# power_converter.net
KiCad netlist of a schematic drawn in EAGLE
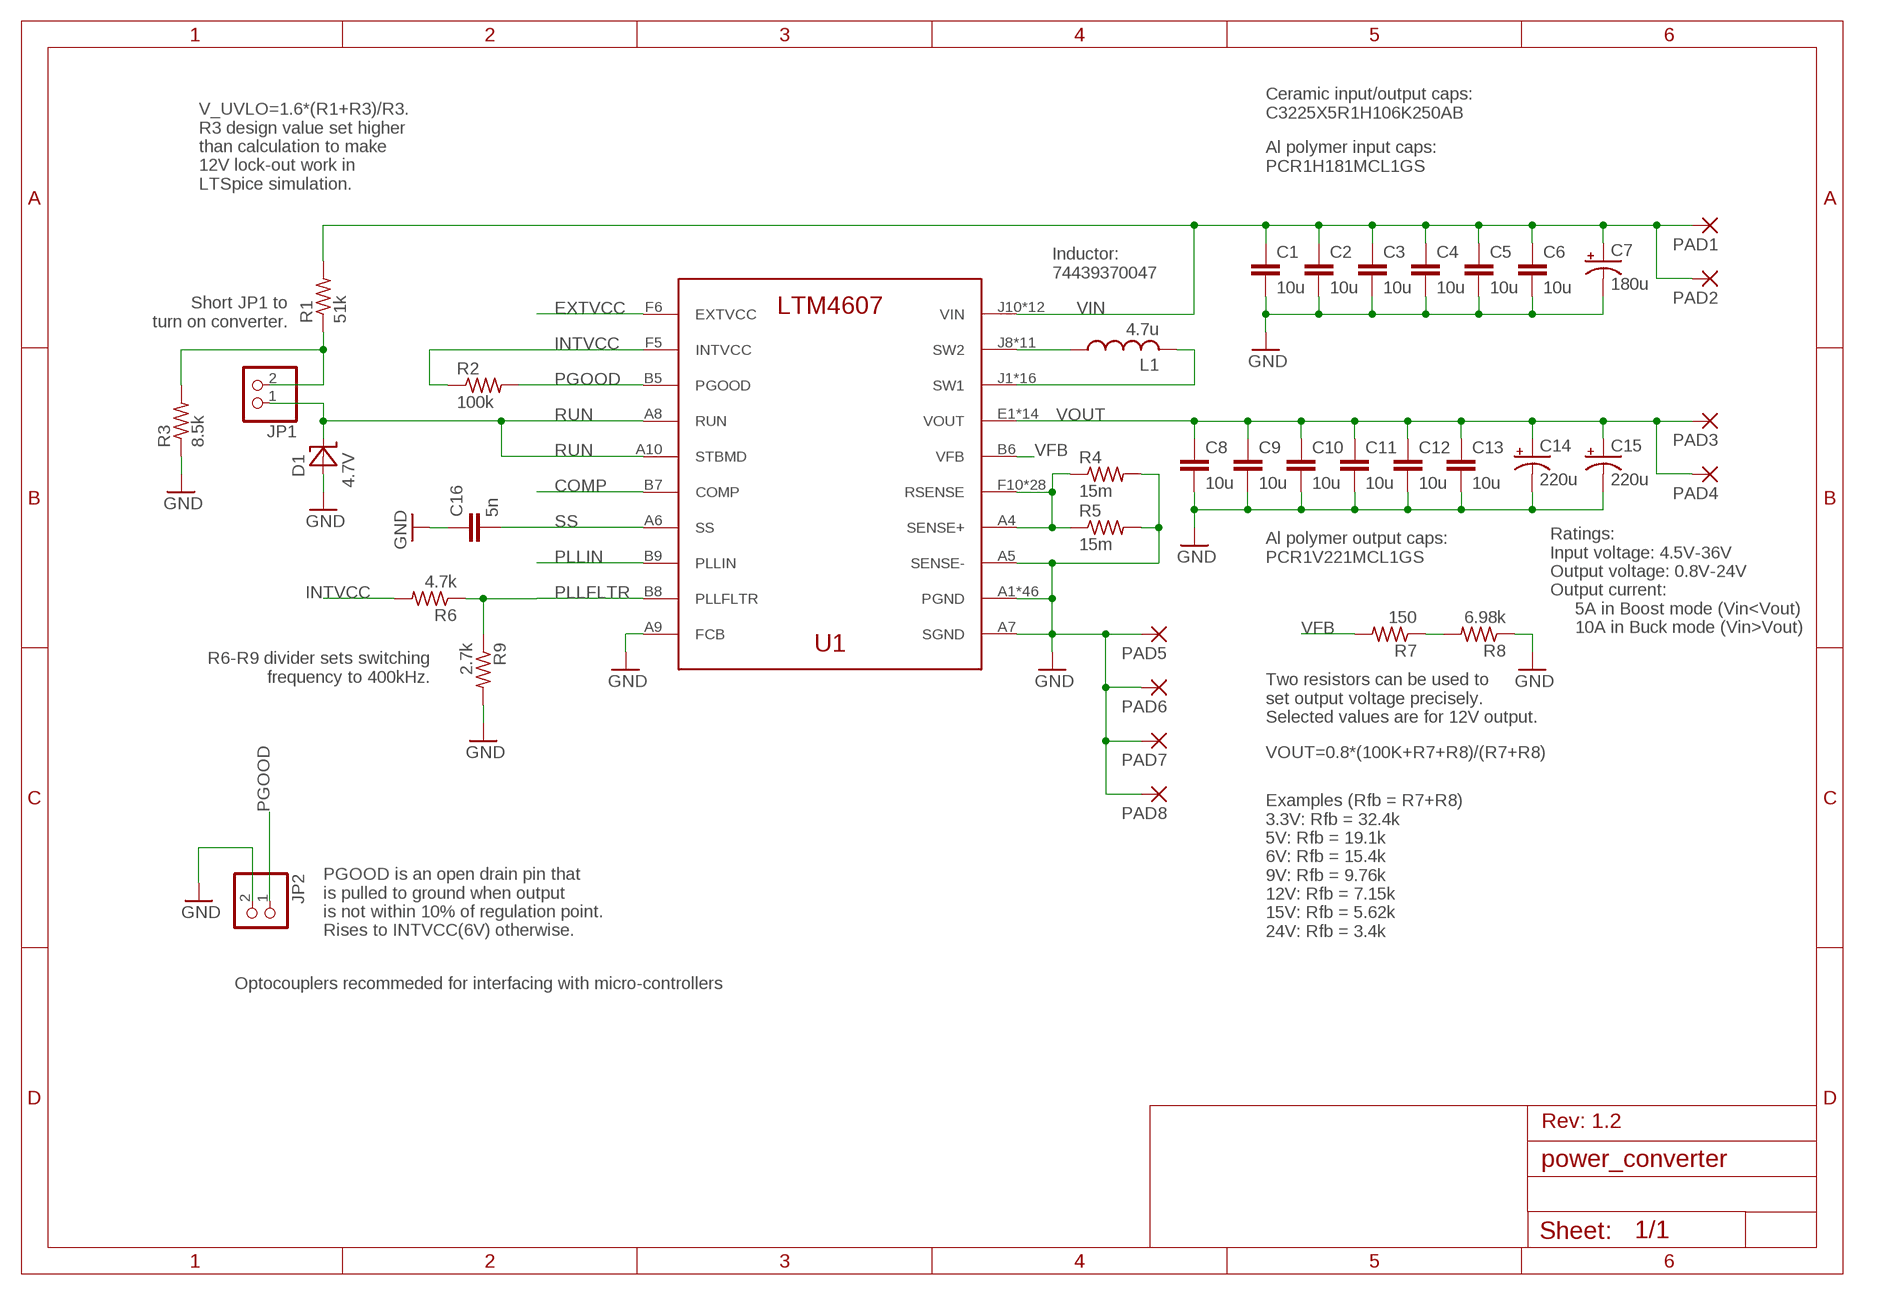
[diagram p0: schematic, sheet 1]

(export (version "E")
  (design (tool "Eeschema 10.0.6"))
  (components
    (comp (ref "C1")
      (value "10u")
      (footprint "eagle-import:C1210")
      (libsource (lib "eagle-import") (part "C-EUC1210"))
    )
    (comp (ref "C2")
      (value "10u")
      (footprint "eagle-import:C1210")
      (libsource (lib "eagle-import") (part "C-EUC1210"))
    )
    (comp (ref "C3")
      (value "10u")
      (footprint "eagle-import:C1210")
      (libsource (lib "eagle-import") (part "C-EUC1210"))
    )
    (comp (ref "C4")
      (value "10u")
      (footprint "eagle-import:C1210")
      (libsource (lib "eagle-import") (part "C-EUC1210"))
    )
    (comp (ref "C5")
      (value "10u")
      (footprint "eagle-import:C1210")
      (libsource (lib "eagle-import") (part "C-EUC1210"))
    )
    (comp (ref "C6")
      (value "10u")
      (footprint "eagle-import:C1210")
      (libsource (lib "eagle-import") (part "C-EUC1210"))
    )
    (comp (ref "C7")
      (value "180u")
      (footprint "eagle-import:PCR1H181MCL1GS")
      (libsource (lib "eagle-import") (part "PCR1H181MCL1GS"))
    )
    (comp (ref "C8")
      (value "10u")
      (footprint "eagle-import:C1210")
      (libsource (lib "eagle-import") (part "C-EUC1210"))
    )
    (comp (ref "C9")
      (value "10u")
      (footprint "eagle-import:C1210")
      (libsource (lib "eagle-import") (part "C-EUC1210"))
    )
    (comp (ref "C10")
      (value "10u")
      (footprint "eagle-import:C1210")
      (libsource (lib "eagle-import") (part "C-EUC1210"))
    )
    (comp (ref "C11")
      (value "10u")
      (footprint "eagle-import:C1210")
      (libsource (lib "eagle-import") (part "C-EUC1210"))
    )
    (comp (ref "C12")
      (value "10u")
      (footprint "eagle-import:C1210")
      (libsource (lib "eagle-import") (part "C-EUC1210"))
    )
    (comp (ref "C13")
      (value "10u")
      (footprint "eagle-import:C1210")
      (libsource (lib "eagle-import") (part "C-EUC1210"))
    )
    (comp (ref "C14")
      (value "220u")
      (footprint "eagle-import:PCR1V221MCL1GS")
      (libsource (lib "eagle-import") (part "PCR1V221MCL1GS"))
    )
    (comp (ref "C15")
      (value "220u")
      (footprint "eagle-import:PCR1V221MCL1GS")
      (libsource (lib "eagle-import") (part "PCR1V221MCL1GS"))
    )
    (comp (ref "C16")
      (value "5n")
      (footprint "eagle-import:C0603")
      (libsource (lib "eagle-import") (part "C-EUC0603"))
    )
    (comp (ref "D1")
      (value "4.7V")
      (footprint "eagle-import:SOT23")
      (libsource (lib "eagle-import") (part "BZX84C4V7LT1G"))
    )
    (comp (ref "JP1")
      (value "PINHD-1X02_2.54-SMD")
      (footprint "eagle-import:1X02SMD")
      (libsource (lib "eagle-import") (part "PINHD-1X02_2.54-SMD"))
    )
    (comp (ref "JP2")
      (value "PINHD-1X02_2.54-SMD")
      (footprint "eagle-import:1X02SMD")
      (libsource (lib "eagle-import") (part "PINHD-1X02_2.54-SMD"))
    )
    (comp (ref "L1")
      (value "4.7u")
      (footprint "eagle-import:74439370047")
      (libsource (lib "eagle-import") (part "74439370047"))
    )
    (comp (ref "PAD1")
      (value "3,81/1,5")
      (footprint "eagle-import:3,81_1,5")
      (libsource (lib "eagle-import") (part "3,81/1,5"))
    )
    (comp (ref "PAD2")
      (value "3,81/1,5")
      (footprint "eagle-import:3,81_1,5")
      (libsource (lib "eagle-import") (part "3,81/1,5"))
    )
    (comp (ref "PAD3")
      (value "3,81/1,5")
      (footprint "eagle-import:3,81_1,5")
      (libsource (lib "eagle-import") (part "3,81/1,5"))
    )
    (comp (ref "PAD4")
      (value "3,81/1,5")
      (footprint "eagle-import:3,81_1,5")
      (libsource (lib "eagle-import") (part "3,81/1,5"))
    )
    (comp (ref "PAD5")
      (value "3,81/1,5")
      (footprint "eagle-import:3,81_1,5")
      (libsource (lib "eagle-import") (part "3,81/1,5"))
    )
    (comp (ref "PAD6")
      (value "3,81/1,5")
      (footprint "eagle-import:3,81_1,5")
      (libsource (lib "eagle-import") (part "3,81/1,5"))
    )
    (comp (ref "PAD7")
      (value "3,81/1,5")
      (footprint "eagle-import:3,81_1,5")
      (libsource (lib "eagle-import") (part "3,81/1,5"))
    )
    (comp (ref "PAD8")
      (value "3,81/1,5")
      (footprint "eagle-import:3,81_1,5")
      (libsource (lib "eagle-import") (part "3,81/1,5"))
    )
    (comp (ref "R1")
      (value "51k")
      (footprint "eagle-import:R0603")
      (libsource (lib "eagle-import") (part "R-US_R0603"))
    )
    (comp (ref "R2")
      (value "100k")
      (footprint "eagle-import:R0603")
      (libsource (lib "eagle-import") (part "R-US_R0603"))
    )
    (comp (ref "R3")
      (value "8.5k")
      (footprint "eagle-import:R0603")
      (libsource (lib "eagle-import") (part "R-US_R0603"))
    )
    (comp (ref "R4")
      (value "15m")
      (footprint "eagle-import:R1206")
      (libsource (lib "eagle-import") (part "R-US_R1206"))
    )
    (comp (ref "R5")
      (value "15m")
      (footprint "eagle-import:R1206")
      (libsource (lib "eagle-import") (part "R-US_R1206"))
    )
    (comp (ref "R6")
      (value "4.7k")
      (footprint "eagle-import:R0603")
      (libsource (lib "eagle-import") (part "R-US_R0603"))
    )
    (comp (ref "R7")
      (value "150")
      (footprint "eagle-import:R0603")
      (libsource (lib "eagle-import") (part "R-US_R0603"))
    )
    (comp (ref "R8")
      (value "6.98k")
      (footprint "eagle-import:R0603")
      (libsource (lib "eagle-import") (part "R-US_R0603"))
    )
    (comp (ref "R9")
      (value "2.7k")
      (footprint "eagle-import:R0603")
      (libsource (lib "eagle-import") (part "R-US_R0603"))
    )
    (comp (ref "U1")
      (value "LTM4607EVPBF")
      (footprint "eagle-import:LGA-141")
      (fields (field (name "MANUFACTURER_PART_NUMBER") "LTM4607EV#PBF"))
      (libsource (lib "eagle-import") (part "LTM4607EVPBF"))
    )
  )
  (nets
    (net (code "1") (name "/COMP") (class "Default")
      (node (ref "U1") (pin "B7") (pinfunction "COMP_B7") (pintype "power_in"))
    )
    (net (code "2") (name "/EXTVCC") (class "Default")
      (node (ref "U1") (pin "F6") (pinfunction "EXTVCC_F6") (pintype "power_in"))
    )
    (net (code "3") (name "/INTVCC") (class "Default")
      (node (ref "R2") (pin "1") (pinfunction "1_1") (pintype "passive"))
      (node (ref "R6") (pin "2") (pinfunction "2_2") (pintype "passive"))
      (node (ref "U1") (pin "F5") (pinfunction "INTVCC_F5") (pintype "power_in"))
    )
    (net (code "4") (name "/PGOOD") (class "Default")
      (node (ref "JP2") (pin "1") (pinfunction "1_1") (pintype "passive"))
      (node (ref "R2") (pin "2") (pinfunction "2_2") (pintype "passive"))
      (node (ref "U1") (pin "B5") (pinfunction "PGOOD_B5") (pintype "power_in"))
    )
    (net (code "5") (name "/PLLFLTR") (class "Default")
      (node (ref "R6") (pin "1") (pinfunction "1_1") (pintype "passive"))
      (node (ref "R9") (pin "1") (pinfunction "1_1") (pintype "passive"))
      (node (ref "U1") (pin "B8") (pinfunction "PLLFLTR_B8") (pintype "power_in"))
    )
    (net (code "6") (name "/PLLIN") (class "Default")
      (node (ref "U1") (pin "B9") (pinfunction "PLLIN_B9") (pintype "power_in"))
    )
    (net (code "7") (name "/RUN") (class "Default")
      (node (ref "D1") (pin "3") (pinfunction "C_3") (pintype "passive"))
      (node (ref "JP1") (pin "1") (pinfunction "1_1") (pintype "passive"))
      (node (ref "U1") (pin "A10") (pinfunction "STBMD_A10") (pintype "power_in"))
      (node (ref "U1") (pin "A8") (pinfunction "RUN_A8") (pintype "power_in"))
    )
    (net (code "8") (name "/SS") (class "Default")
      (node (ref "C16") (pin "2") (pinfunction "2_2") (pintype "passive"))
      (node (ref "U1") (pin "A6") (pinfunction "SS_A6") (pintype "power_in"))
    )
    (net (code "9") (name "/VFB") (class "Default")
      (node (ref "R7") (pin "2") (pinfunction "2_2") (pintype "passive"))
      (node (ref "U1") (pin "B6") (pinfunction "VFB_B6") (pintype "power_in"))
    )
    (net (code "10") (name "/VIN") (class "Default")
      (node (ref "C1") (pin "1") (pinfunction "1_1") (pintype "passive"))
      (node (ref "C2") (pin "1") (pinfunction "1_1") (pintype "passive"))
      (node (ref "C3") (pin "1") (pinfunction "1_1") (pintype "passive"))
      (node (ref "C4") (pin "1") (pinfunction "1_1") (pintype "passive"))
      (node (ref "C5") (pin "1") (pinfunction "1_1") (pintype "passive"))
      (node (ref "C6") (pin "1") (pinfunction "1_1") (pintype "passive"))
      (node (ref "C7") (pin "POS") (pinfunction "+_POS") (pintype "passive"))
      (node (ref "PAD1") (pin "1") (pinfunction "P_1") (pintype "passive"))
      (node (ref "PAD2") (pin "1") (pinfunction "P_1") (pintype "passive"))
      (node (ref "R1") (pin "2") (pinfunction "2_2") (pintype "passive"))
      (node (ref "U1") (pin "J10") (pinfunction "VIN_J10") (pintype "power_in"))
      (node (ref "U1") (pin "J11") (pinfunction "VIN_J11") (pintype "power_in"))
      (node (ref "U1") (pin "J12") (pinfunction "VIN_J12") (pintype "power_in"))
      (node (ref "U1") (pin "K10") (pinfunction "VIN_K10") (pintype "power_in"))
      (node (ref "U1") (pin "K11") (pinfunction "VIN_K11") (pintype "power_in"))
      (node (ref "U1") (pin "K12") (pinfunction "VIN_K12") (pintype "power_in"))
      (node (ref "U1") (pin "L10") (pinfunction "VIN_L10") (pintype "power_in"))
      (node (ref "U1") (pin "L11") (pinfunction "VIN_L11") (pintype "power_in"))
      (node (ref "U1") (pin "L12") (pinfunction "VIN_L12") (pintype "power_in"))
      (node (ref "U1") (pin "M10") (pinfunction "VIN_M10") (pintype "power_in"))
      (node (ref "U1") (pin "M11") (pinfunction "VIN_M11") (pintype "power_in"))
      (node (ref "U1") (pin "M12") (pinfunction "VIN_M12") (pintype "power_in"))
    )
    (net (code "11") (name "/VOUT") (class "Default")
      (node (ref "C10") (pin "1") (pinfunction "1_1") (pintype "passive"))
      (node (ref "C11") (pin "1") (pinfunction "1_1") (pintype "passive"))
      (node (ref "C12") (pin "1") (pinfunction "1_1") (pintype "passive"))
      (node (ref "C13") (pin "1") (pinfunction "1_1") (pintype "passive"))
      (node (ref "C14") (pin "POS") (pinfunction "+_POS") (pintype "passive"))
      (node (ref "C15") (pin "POS") (pinfunction "+_POS") (pintype "passive"))
      (node (ref "C8") (pin "1") (pinfunction "1_1") (pintype "passive"))
      (node (ref "C9") (pin "1") (pinfunction "1_1") (pintype "passive"))
      (node (ref "PAD3") (pin "1") (pinfunction "P_1") (pintype "passive"))
      (node (ref "PAD4") (pin "1") (pinfunction "P_1") (pintype "passive"))
      (node (ref "U1") (pin "E1") (pinfunction "VOUT_E1") (pintype "power_in"))
      (node (ref "U1") (pin "E2") (pinfunction "VOUT_E2") (pintype "power_in"))
      (node (ref "U1") (pin "F1") (pinfunction "VOUT_F1") (pintype "power_in"))
      (node (ref "U1") (pin "F2") (pinfunction "VOUT_F2") (pintype "power_in"))
      (node (ref "U1") (pin "F3") (pinfunction "VOUT_F3") (pintype "power_in"))
      (node (ref "U1") (pin "F4") (pinfunction "VOUT_F4") (pintype "power_in"))
      (node (ref "U1") (pin "G1") (pinfunction "VOUT_G1") (pintype "power_in"))
      (node (ref "U1") (pin "G2") (pinfunction "VOUT_G2") (pintype "power_in"))
      (node (ref "U1") (pin "G3") (pinfunction "VOUT_G3") (pintype "power_in"))
      (node (ref "U1") (pin "G4") (pinfunction "VOUT_G4") (pintype "power_in"))
      (node (ref "U1") (pin "H1") (pinfunction "VOUT_H1") (pintype "power_in"))
      (node (ref "U1") (pin "H2") (pinfunction "VOUT_H2") (pintype "power_in"))
      (node (ref "U1") (pin "H3") (pinfunction "VOUT_H3") (pintype "power_in"))
      (node (ref "U1") (pin "H4") (pinfunction "VOUT_H4") (pintype "power_in"))
    )
    (net (code "12") (name "GND") (class "Default")
      (node (ref "C1") (pin "2") (pinfunction "2_2") (pintype "passive"))
      (node (ref "C10") (pin "2") (pinfunction "2_2") (pintype "passive"))
      (node (ref "C11") (pin "2") (pinfunction "2_2") (pintype "passive"))
      (node (ref "C12") (pin "2") (pinfunction "2_2") (pintype "passive"))
      (node (ref "C13") (pin "2") (pinfunction "2_2") (pintype "passive"))
      (node (ref "C14") (pin "NEG") (pinfunction "-_NEG") (pintype "passive"))
      (node (ref "C15") (pin "NEG") (pinfunction "-_NEG") (pintype "passive"))
      (node (ref "C16") (pin "1") (pinfunction "1_1") (pintype "passive"))
      (node (ref "C2") (pin "2") (pinfunction "2_2") (pintype "passive"))
      (node (ref "C3") (pin "2") (pinfunction "2_2") (pintype "passive"))
      (node (ref "C4") (pin "2") (pinfunction "2_2") (pintype "passive"))
      (node (ref "C5") (pin "2") (pinfunction "2_2") (pintype "passive"))
      (node (ref "C6") (pin "2") (pinfunction "2_2") (pintype "passive"))
      (node (ref "C7") (pin "NEG") (pinfunction "-_NEG") (pintype "passive"))
      (node (ref "C8") (pin "2") (pinfunction "2_2") (pintype "passive"))
      (node (ref "C9") (pin "2") (pinfunction "2_2") (pintype "passive"))
      (node (ref "D1") (pin "1") (pinfunction "A_1") (pintype "passive"))
      (node (ref "JP2") (pin "2") (pinfunction "2_2") (pintype "passive"))
      (node (ref "PAD5") (pin "1") (pinfunction "P_1") (pintype "passive"))
      (node (ref "PAD6") (pin "1") (pinfunction "P_1") (pintype "passive"))
      (node (ref "PAD7") (pin "1") (pinfunction "P_1") (pintype "passive"))
      (node (ref "PAD8") (pin "1") (pinfunction "P_1") (pintype "passive"))
      (node (ref "R3") (pin "1") (pinfunction "1_1") (pintype "passive"))
      (node (ref "R4") (pin "2") (pinfunction "2_2") (pintype "passive"))
      (node (ref "R5") (pin "2") (pinfunction "2_2") (pintype "passive"))
      (node (ref "R8") (pin "1") (pinfunction "1_1") (pintype "passive"))
      (node (ref "R9") (pin "2") (pinfunction "2_2") (pintype "passive"))
      (node (ref "U1") (pin "A1") (pinfunction "PGND_A1") (pintype "power_in"))
      (node (ref "U1") (pin "A11") (pinfunction "PGND_A11") (pintype "power_in"))
      (node (ref "U1") (pin "A12") (pinfunction "PGND_A12") (pintype "power_in"))
      (node (ref "U1") (pin "A2") (pinfunction "PGND_A2") (pintype "power_in"))
      (node (ref "U1") (pin "A3") (pinfunction "PGND_A3") (pintype "power_in"))
      (node (ref "U1") (pin "A5") (pinfunction "SENSE-_A5") (pintype "power_in"))
      (node (ref "U1") (pin "A7") (pinfunction "SGND_A7") (pintype "power_in"))
      (node (ref "U1") (pin "A9") (pinfunction "FCB_A9") (pintype "power_in"))
      (node (ref "U1") (pin "B1") (pinfunction "PGND_B1") (pintype "power_in"))
      (node (ref "U1") (pin "B10") (pinfunction "PGND_B10") (pintype "power_in"))
      (node (ref "U1") (pin "B11") (pinfunction "PGND_B11") (pintype "power_in"))
      (node (ref "U1") (pin "B12") (pinfunction "PGND_B12") (pintype "power_in"))
      (node (ref "U1") (pin "B2") (pinfunction "PGND_B2") (pintype "power_in"))
      (node (ref "U1") (pin "B3") (pinfunction "PGND_B3") (pintype "power_in"))
      (node (ref "U1") (pin "B4") (pinfunction "PGND_B4") (pintype "power_in"))
      (node (ref "U1") (pin "C1") (pinfunction "PGND_C1") (pintype "power_in"))
      (node (ref "U1") (pin "C10") (pinfunction "PGND_C10") (pintype "power_in"))
      (node (ref "U1") (pin "C11") (pinfunction "PGND_C11") (pintype "power_in"))
      (node (ref "U1") (pin "C12") (pinfunction "PGND_C12") (pintype "power_in"))
      (node (ref "U1") (pin "C2") (pinfunction "PGND_C2") (pintype "power_in"))
      (node (ref "U1") (pin "C3") (pinfunction "PGND_C3") (pintype "power_in"))
      (node (ref "U1") (pin "C4") (pinfunction "PGND_C4") (pintype "power_in"))
      (node (ref "U1") (pin "C5") (pinfunction "PGND_C5") (pintype "power_in"))
      (node (ref "U1") (pin "C6") (pinfunction "PGND_C6") (pintype "power_in"))
      (node (ref "U1") (pin "C7") (pinfunction "PGND_C7") (pintype "power_in"))
      (node (ref "U1") (pin "C8") (pinfunction "PGND_C8") (pintype "power_in"))
      (node (ref "U1") (pin "C9") (pinfunction "PGND_C9") (pintype "power_in"))
      (node (ref "U1") (pin "D1") (pinfunction "PGND_D1") (pintype "power_in"))
      (node (ref "U1") (pin "D10") (pinfunction "PGND_D10") (pintype "power_in"))
      (node (ref "U1") (pin "D11") (pinfunction "PGND_D11") (pintype "power_in"))
      (node (ref "U1") (pin "D12") (pinfunction "PGND_D12") (pintype "power_in"))
      (node (ref "U1") (pin "D2") (pinfunction "PGND_D2") (pintype "power_in"))
      (node (ref "U1") (pin "D3") (pinfunction "PGND_D3") (pintype "power_in"))
      (node (ref "U1") (pin "D4") (pinfunction "PGND_D4") (pintype "power_in"))
      (node (ref "U1") (pin "D5") (pinfunction "PGND_D5") (pintype "power_in"))
      (node (ref "U1") (pin "D6") (pinfunction "PGND_D6") (pintype "power_in"))
      (node (ref "U1") (pin "D7") (pinfunction "PGND_D7") (pintype "power_in"))
      (node (ref "U1") (pin "D8") (pinfunction "PGND_D8") (pintype "power_in"))
      (node (ref "U1") (pin "D9") (pinfunction "PGND_D9") (pintype "power_in"))
      (node (ref "U1") (pin "E10") (pinfunction "PGND_E10") (pintype "power_in"))
      (node (ref "U1") (pin "E11") (pinfunction "PGND_E11") (pintype "power_in"))
      (node (ref "U1") (pin "E12") (pinfunction "PGND_E12") (pintype "power_in"))
      (node (ref "U1") (pin "E3") (pinfunction "PGND_E3") (pintype "power_in"))
      (node (ref "U1") (pin "E4") (pinfunction "PGND_E4") (pintype "power_in"))
      (node (ref "U1") (pin "E5") (pinfunction "PGND_E5") (pintype "power_in"))
      (node (ref "U1") (pin "E6") (pinfunction "PGND_E6") (pintype "power_in"))
      (node (ref "U1") (pin "E7") (pinfunction "PGND_E7") (pintype "power_in"))
      (node (ref "U1") (pin "E8") (pinfunction "PGND_E8") (pintype "power_in"))
      (node (ref "U1") (pin "E9") (pinfunction "PGND_E9") (pintype "power_in"))
    )
    (net (code "13") (name "Net-(JP1-Pad2)") (class "Default")
      (node (ref "JP1") (pin "2") (pinfunction "2_2") (pintype "passive"))
      (node (ref "R1") (pin "1") (pinfunction "1_1") (pintype "passive"))
      (node (ref "R3") (pin "2") (pinfunction "2_2") (pintype "passive"))
    )
    (net (code "14") (name "Net-(L1-1)") (class "Default")
      (node (ref "L1") (pin "M1") (pinfunction "1_M1") (pintype "passive"))
      (node (ref "U1") (pin "J8") (pinfunction "SW2_J8") (pintype "power_in"))
      (node (ref "U1") (pin "J9") (pinfunction "SW2_J9") (pintype "power_in"))
      (node (ref "U1") (pin "K7") (pinfunction "SW2_K7") (pintype "power_in"))
      (node (ref "U1") (pin "K8") (pinfunction "SW2_K8") (pintype "power_in"))
      (node (ref "U1") (pin "K9") (pinfunction "SW2_K9") (pintype "power_in"))
      (node (ref "U1") (pin "L7") (pinfunction "SW2_L7") (pintype "power_in"))
      (node (ref "U1") (pin "L8") (pinfunction "SW2_L8") (pintype "power_in"))
      (node (ref "U1") (pin "L9") (pinfunction "SW2_L9") (pintype "power_in"))
      (node (ref "U1") (pin "M7") (pinfunction "SW2_M7") (pintype "power_in"))
      (node (ref "U1") (pin "M8") (pinfunction "SW2_M8") (pintype "power_in"))
      (node (ref "U1") (pin "M9") (pinfunction "SW2_M9") (pintype "power_in"))
    )
    (net (code "15") (name "Net-(L1-2)") (class "Default")
      (node (ref "L1") (pin "M2") (pinfunction "2_M2") (pintype "passive"))
      (node (ref "U1") (pin "J1") (pinfunction "SW1_J1") (pintype "power_in"))
      (node (ref "U1") (pin "J2") (pinfunction "SW1_J2") (pintype "power_in"))
      (node (ref "U1") (pin "J3") (pinfunction "SW1_J3") (pintype "power_in"))
      (node (ref "U1") (pin "J4") (pinfunction "SW1_J4") (pintype "power_in"))
      (node (ref "U1") (pin "K1") (pinfunction "SW1_K1") (pintype "power_in"))
      (node (ref "U1") (pin "K2") (pinfunction "SW1_K2") (pintype "power_in"))
      (node (ref "U1") (pin "K3") (pinfunction "SW1_K3") (pintype "power_in"))
      (node (ref "U1") (pin "K4") (pinfunction "SW1_K4") (pintype "power_in"))
      (node (ref "U1") (pin "L1") (pinfunction "SW1_L1") (pintype "power_in"))
      (node (ref "U1") (pin "L2") (pinfunction "SW1_L2") (pintype "power_in"))
      (node (ref "U1") (pin "L3") (pinfunction "SW1_L3") (pintype "power_in"))
      (node (ref "U1") (pin "L4") (pinfunction "SW1_L4") (pintype "power_in"))
      (node (ref "U1") (pin "M1") (pinfunction "SW1_M1") (pintype "power_in"))
      (node (ref "U1") (pin "M2") (pinfunction "SW1_M2") (pintype "power_in"))
      (node (ref "U1") (pin "M3") (pinfunction "SW1_M3") (pintype "power_in"))
      (node (ref "U1") (pin "M4") (pinfunction "SW1_M4") (pintype "power_in"))
    )
    (net (code "16") (name "Net-(R7-Pad1)") (class "Default")
      (node (ref "R7") (pin "1") (pinfunction "1_1") (pintype "passive"))
      (node (ref "R8") (pin "2") (pinfunction "2_2") (pintype "passive"))
    )
    (net (code "17") (name "Net-(U1-SENSE+)") (class "Default")
      (node (ref "R4") (pin "1") (pinfunction "1_1") (pintype "passive"))
      (node (ref "R5") (pin "1") (pinfunction "1_1") (pintype "passive"))
      (node (ref "U1") (pin "A4") (pinfunction "SENSE+_A4") (pintype "power_in"))
      (node (ref "U1") (pin "F10") (pinfunction "RSENSE_F10") (pintype "power_in"))
      (node (ref "U1") (pin "F11") (pinfunction "RSENSE_F11") (pintype "power_in"))
      (node (ref "U1") (pin "F12") (pinfunction "RSENSE_F12") (pintype "power_in"))
      (node (ref "U1") (pin "G10") (pinfunction "RSENSE_G10") (pintype "power_in"))
      (node (ref "U1") (pin "G11") (pinfunction "RSENSE_G11") (pintype "power_in"))
      (node (ref "U1") (pin "G12") (pinfunction "RSENSE_G12") (pintype "power_in"))
      (node (ref "U1") (pin "G5") (pinfunction "RSENSE_G5") (pintype "power_in"))
      (node (ref "U1") (pin "G6") (pinfunction "RSENSE_G6") (pintype "power_in"))
      (node (ref "U1") (pin "G7") (pinfunction "RSENSE_G7") (pintype "power_in"))
      (node (ref "U1") (pin "G8") (pinfunction "RSENSE_G8") (pintype "power_in"))
      (node (ref "U1") (pin "G9") (pinfunction "RSENSE_G9") (pintype "power_in"))
      (node (ref "U1") (pin "H10") (pinfunction "RSENSE_H10") (pintype "power_in"))
      (node (ref "U1") (pin "H11") (pinfunction "RSENSE_H11") (pintype "power_in"))
      (node (ref "U1") (pin "H12") (pinfunction "RSENSE_H12") (pintype "power_in"))
      (node (ref "U1") (pin "H5") (pinfunction "RSENSE_H5") (pintype "power_in"))
      (node (ref "U1") (pin "H6") (pinfunction "RSENSE_H6") (pintype "power_in"))
      (node (ref "U1") (pin "H7") (pinfunction "RSENSE_H7") (pintype "power_in"))
      (node (ref "U1") (pin "H8") (pinfunction "RSENSE_H8") (pintype "power_in"))
      (node (ref "U1") (pin "H9") (pinfunction "RSENSE_H9") (pintype "power_in"))
      (node (ref "U1") (pin "J5") (pinfunction "RSENSE_J5") (pintype "power_in"))
      (node (ref "U1") (pin "J6") (pinfunction "RSENSE_J6") (pintype "power_in"))
      (node (ref "U1") (pin "J7") (pinfunction "RSENSE_J7") (pintype "power_in"))
      (node (ref "U1") (pin "K5") (pinfunction "RSENSE_K5") (pintype "power_in"))
      (node (ref "U1") (pin "K6") (pinfunction "RSENSE_K6") (pintype "power_in"))
      (node (ref "U1") (pin "L5") (pinfunction "RSENSE_L5") (pintype "power_in"))
      (node (ref "U1") (pin "L6") (pinfunction "RSENSE_L6") (pintype "power_in"))
      (node (ref "U1") (pin "M5") (pinfunction "RSENSE_M5") (pintype "power_in"))
      (node (ref "U1") (pin "M6") (pinfunction "RSENSE_M6") (pintype "power_in"))
    )
  )
)
